# dl3.net
KiCad netlist of a schematic drawn in EAGLE
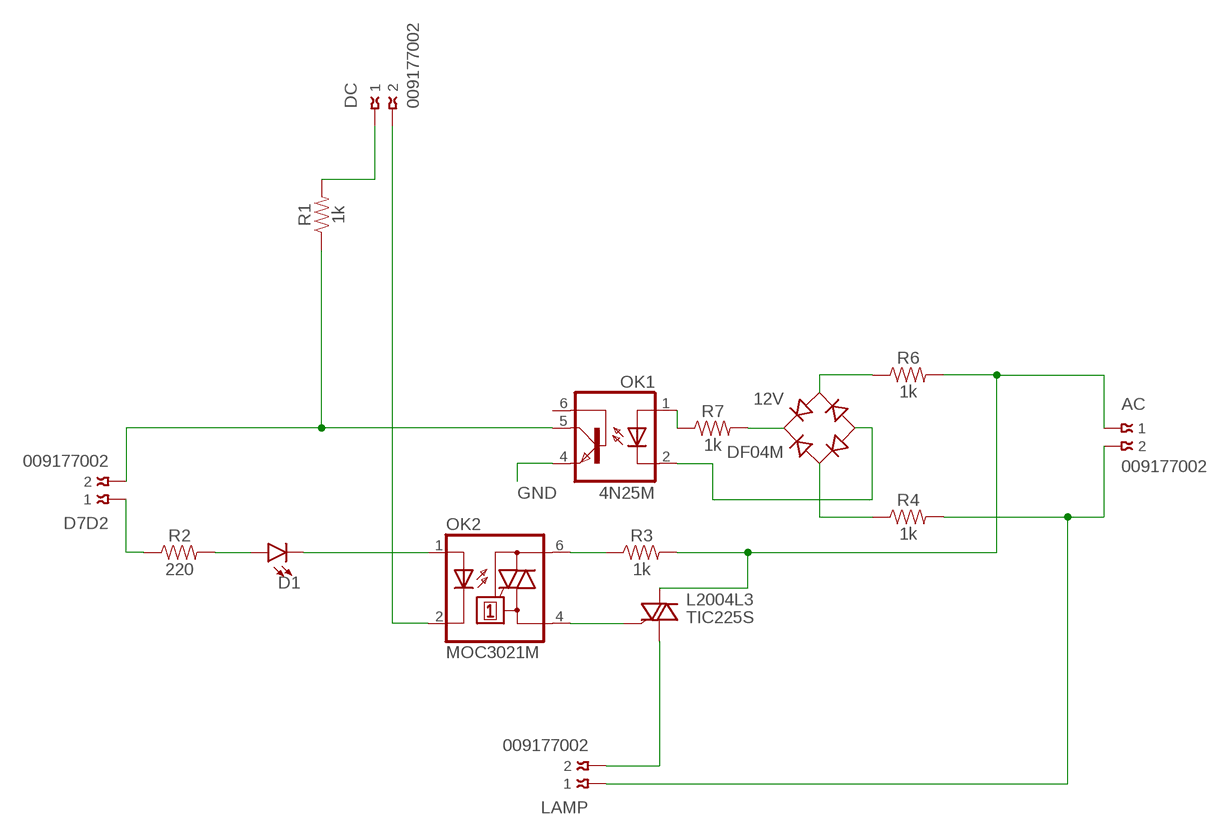
[diagram p0: schematic, sheet 1]

(export (version "E")
  (design (tool "Eeschema 10.0.6"))
  (components
    (comp (ref "AC")
      (value "009177002")
      (footprint "eagle-import:009177002")
      (fields (field (name "MPN") "009177002001006"))
      (libsource (lib "eagle-import") (part "00917?0027"))
    )
    (comp (ref "D1")
      (value "LED1206")
      (footprint "eagle-import:LED-1206")
      (libsource (lib "eagle-import") (part "LED1206"))
    )
    (comp (ref "D7D2")
      (value "009177002")
      (footprint "eagle-import:009177002")
      (fields (field (name "MPN") "009177002001006"))
      (libsource (lib "eagle-import") (part "00917?0027"))
    )
    (comp (ref "DC")
      (value "009177002")
      (footprint "eagle-import:009177002")
      (fields (field (name "MPN") "009177002001006"))
      (libsource (lib "eagle-import") (part "00917?0027"))
    )
    (comp (ref "DF04M")
      (value "12V")
      (footprint "eagle-import:B-DIL")
      (libsource (lib "eagle-import") (part "B-DIL"))
    )
    (comp (ref "L2004L3")
      (value "TIC225S")
      (footprint "eagle-import:TO220DS")
      (libsource (lib "eagle-import") (part "TIC225S"))
    )
    (comp (ref "LAMP")
      (value "009177002")
      (footprint "eagle-import:009177002")
      (fields (field (name "MPN") "009177002001006"))
      (libsource (lib "eagle-import") (part "00917?0027"))
    )
    (comp (ref "OK1")
      (value "4N25M")
      (footprint "eagle-import:DIL06")
      (fields (field (name "MPN") "4N25-M"))
      (libsource (lib "eagle-import") (part "4N?M25"))
    )
    (comp (ref "OK2")
      (value "MOC3021M")
      (footprint "eagle-import:DIL06")
      (fields (field (name "MF") "FAIRCHILD SEMICONDUCTOR") (field (name "MPN") "MOC3021-M"))
      (libsource (lib "eagle-import") (part "MOC30M21"))
    )
    (comp (ref "R1")
      (value "1k")
      (footprint "eagle-import:AXIAL-0.3")
      (libsource (lib "eagle-import") (part "1KOHM-HORIZ-1/4W-1%"))
    )
    (comp (ref "R2")
      (value "220")
      (footprint "eagle-import:0805")
      (libsource (lib "eagle-import") (part "0.75OHM-0805-1/4W-1%"))
    )
    (comp (ref "R3")
      (value "1k")
      (footprint "eagle-import:AXIAL-0.3")
      (libsource (lib "eagle-import") (part "1KOHM-HORIZ-1/4W-1%"))
    )
    (comp (ref "R4")
      (value "1k")
      (footprint "eagle-import:AXIAL-0.3")
      (libsource (lib "eagle-import") (part "1KOHM-HORIZ-1/4W-1%"))
    )
    (comp (ref "R6")
      (value "1k")
      (footprint "eagle-import:AXIAL-0.3")
      (libsource (lib "eagle-import") (part "1KOHM-HORIZ-1/4W-1%"))
    )
    (comp (ref "R7")
      (value "1k")
      (footprint "eagle-import:0805")
      (libsource (lib "eagle-import") (part "0.75OHM-0805-1/4W-1%"))
    )
  )
  (nets
    (net (code "1") (name "/GND") (class "Default")
      (node (ref "AC") (pin "2") (pinfunction "2_2") (pintype "passive"))
      (node (ref "LAMP") (pin "1") (pinfunction "1_1") (pintype "passive"))
      (node (ref "OK1") (pin "4") (pinfunction "EMI_4") (pintype "passive"))
      (node (ref "R4") (pin "P$2") (pinfunction "2_P$2") (pintype "passive"))
    )
    (net (code "2") (name "Net-(D1-PadA)") (class "Default")
      (node (ref "D1") (pin "A") (pinfunction "A_A") (pintype "passive"))
      (node (ref "R2") (pin "2") (pinfunction "2_2") (pintype "passive"))
    )
    (net (code "3") (name "Net-(D7D2-Pad1)") (class "Default")
      (node (ref "D7D2") (pin "1") (pinfunction "1_1") (pintype "passive"))
      (node (ref "R2") (pin "1") (pinfunction "1_1") (pintype "passive"))
    )
    (net (code "4") (name "Net-(DF04M-Pad+)") (class "Default")
      (node (ref "DF04M") (pin "+") (pinfunction "+_+") (pintype "passive"))
      (node (ref "R7") (pin "2") (pinfunction "2_2") (pintype "passive"))
    )
    (net (code "5") (name "Net-(L2004L3-PadA1)") (class "Default")
      (node (ref "L2004L3") (pin "A1") (pinfunction "A1_A1") (pintype "passive"))
      (node (ref "LAMP") (pin "2") (pinfunction "2_2") (pintype "passive"))
    )
    (net (code "6") (name "Net-(OK1-A)") (class "Default")
      (node (ref "OK1") (pin "1") (pinfunction "A_1") (pintype "passive"))
      (node (ref "R7") (pin "1") (pinfunction "1_1") (pintype "passive"))
    )
    (net (code "7") (name "Net-(OK1-C)") (class "Default")
      (node (ref "DF04M") (pin "-") (pinfunction "-_-") (pintype "passive"))
      (node (ref "OK1") (pin "2") (pinfunction "C_2") (pintype "passive"))
    )
    (net (code "8") (name "Net-(OK1-COL)") (class "Default")
      (node (ref "D7D2") (pin "2") (pinfunction "2_2") (pintype "passive"))
      (node (ref "OK1") (pin "5") (pinfunction "COL_5") (pintype "passive"))
      (node (ref "R1") (pin "P$1") (pinfunction "1_P$1") (pintype "passive"))
    )
    (net (code "9") (name "Net-(OK2-A)") (class "Default")
      (node (ref "D1") (pin "C") (pinfunction "C_C") (pintype "passive"))
      (node (ref "OK2") (pin "1") (pinfunction "A_1") (pintype "passive"))
    )
    (net (code "10") (name "Net-(OK2-A1)") (class "Default")
      (node (ref "L2004L3") (pin "G") (pinfunction "G_G") (pintype "passive"))
      (node (ref "OK2") (pin "4") (pinfunction "A1_4") (pintype "passive"))
    )
    (net (code "11") (name "Net-(OK2-A2)") (class "Default")
      (node (ref "OK2") (pin "6") (pinfunction "A2_6") (pintype "passive"))
      (node (ref "R3") (pin "P$1") (pinfunction "1_P$1") (pintype "passive"))
    )
    (net (code "12") (name "Net-(OK2-C)") (class "Default")
      (node (ref "DC") (pin "2") (pinfunction "2_2") (pintype "passive"))
      (node (ref "OK2") (pin "2") (pinfunction "C_2") (pintype "passive"))
    )
    (net (code "13") (name "Net-(R1-2)") (class "Default")
      (node (ref "DC") (pin "1") (pinfunction "1_1") (pintype "passive"))
      (node (ref "R1") (pin "P$2") (pinfunction "2_P$2") (pintype "passive"))
    )
    (net (code "14") (name "Net-(R3-2)") (class "Default")
      (node (ref "AC") (pin "1") (pinfunction "1_1") (pintype "passive"))
      (node (ref "L2004L3") (pin "A2") (pinfunction "A2_A2") (pintype "passive"))
      (node (ref "R3") (pin "P$2") (pinfunction "2_P$2") (pintype "passive"))
      (node (ref "R6") (pin "P$2") (pinfunction "2_P$2") (pintype "passive"))
    )
    (net (code "15") (name "Net-(R4-1)") (class "Default")
      (node (ref "DF04M") (pin "AC1") (pinfunction "AC1_AC1") (pintype "passive"))
      (node (ref "R4") (pin "P$1") (pinfunction "1_P$1") (pintype "passive"))
    )
    (net (code "16") (name "Net-(R6-1)") (class "Default")
      (node (ref "DF04M") (pin "AC2") (pinfunction "AC2_AC2") (pintype "passive"))
      (node (ref "R6") (pin "P$1") (pinfunction "1_P$1") (pintype "passive"))
    )
    (net (code "17") (name "unconnected-(OK1-BAS-Pad6)") (class "Default")
      (node (ref "OK1") (pin "6") (pinfunction "BAS_6") (pintype "passive"))
    )
  )
)
